# switch-backpack.net
KiCad netlist of a schematic drawn in EAGLE
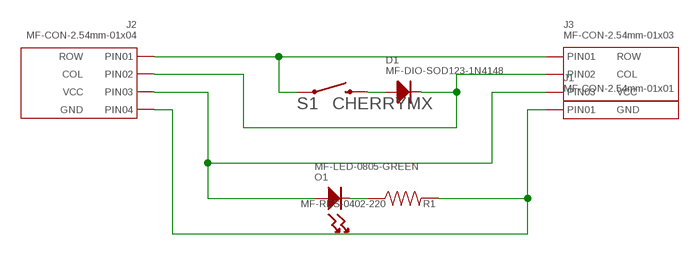
[diagram p0: schematic, sheet 1]

(export (version "E")
  (design (tool "Eeschema 10.0.6"))
  (components
    (comp (ref "D1")
      (value "MF-DIO-SOD123-1N4148")
      (footprint "eagle-import:SOD-123")
      (fields (field (name "HOUSEPART") "YES"))
      (libsource (lib "eagle-import") (part "DIODES_SOD-123_1N4148"))
    )
    (comp (ref "J1")
      (value "MF-CON-2.54mm-01x01")
      (footprint "eagle-import:PTH_2.54MM_01X01")
      (fields (field (name "HOUSEPART") "YES") (field (name "LABEL01") "GND"))
      (libsource (lib "eagle-import") (part "CON_01X01_PTH_2.54MM"))
    )
    (comp (ref "J2")
      (value "MF-CON-2.54mm-01x04")
      (footprint "eagle-import:PTH_2.54MM_01X04")
      (fields
        (field (name "HOUSEPART") "YES")
        (field (name "LABEL01") "ROW")
        (field (name "LABEL02") "COL")
        (field (name "LABEL03") "VCC")
        (field (name "LABEL04") "GND")
      )
      (libsource (lib "eagle-import") (part "CON_01X04_PTH_2.54MM"))
    )
    (comp (ref "J3")
      (value "MF-CON-2.54mm-01x03")
      (footprint "eagle-import:PTH_2.54MM_01X03")
      (fields
        (field (name "HOUSEPART") "YES")
        (field (name "LABEL01") "ROW")
        (field (name "LABEL02") "COL")
        (field (name "LABEL03") "VCC")
      )
      (libsource (lib "eagle-import") (part "CON_01X03_PTH_2.54MM"))
    )
    (comp (ref "O1")
      (value "MF-LED-0805-GREEN")
      (footprint "eagle-import:LED0805")
      (fields (field (name "HOUSEPART") "NO"))
      (libsource (lib "eagle-import") (part "LED_SINGLE-0805"))
    )
    (comp (ref "R1")
      (value "MF-RES-0402-220")
      (footprint "eagle-import:R0402")
      (libsource (lib "eagle-import") (part "RESISTOR_0402"))
    )
    (comp (ref "S1")
      (value "CHERRYMX")
      (footprint "eagle-import:CHERRYMX")
      (libsource (lib "eagle-import") (part "SWITCH-MOMENTARY-2CHERRYMX"))
    )
  )
  (nets
    (net (code "1") (name "Net-(J1-PIN1)") (class "Default")
      (node (ref "J1") (pin "P$1") (pinfunction "PIN1_P$1") (pintype "bidirectional"))
      (node (ref "J2") (pin "P$4") (pinfunction "PIN4_P$4") (pintype "bidirectional"))
      (node (ref "R1") (pin "P$2") (pinfunction "P$2_P$2") (pintype "passive"))
    )
    (net (code "2") (name "Net-(J2-PIN1)") (class "Default")
      (node (ref "J2") (pin "P$1") (pinfunction "PIN1_P$1") (pintype "bidirectional"))
      (node (ref "J3") (pin "P$1") (pinfunction "PIN1_P$1") (pintype "bidirectional"))
      (node (ref "S1") (pin "P$1") (pinfunction "1_P$1") (pintype "passive"))
    )
    (net (code "3") (name "Net-(J2-PIN2)") (class "Default")
      (node (ref "D1") (pin "CATHODE") (pinfunction "CATHODE_CATHODE") (pintype "bidirectional"))
      (node (ref "J2") (pin "P$2") (pinfunction "PIN2_P$2") (pintype "bidirectional"))
      (node (ref "J3") (pin "P$2") (pinfunction "PIN2_P$2") (pintype "bidirectional"))
    )
    (net (code "4") (name "Net-(J2-PIN3)") (class "Default")
      (node (ref "J2") (pin "P$3") (pinfunction "PIN3_P$3") (pintype "bidirectional"))
      (node (ref "J3") (pin "P$3") (pinfunction "PIN3_P$3") (pintype "bidirectional"))
      (node (ref "O1") (pin "ANODE") (pinfunction "ANODE_ANODE") (pintype "power_in"))
    )
    (net (code "5") (name "Net-(O1-PadCATHODE)") (class "Default")
      (node (ref "O1") (pin "CATHODE") (pinfunction "CATHODE_CATHODE") (pintype "power_in"))
      (node (ref "R1") (pin "P$1") (pinfunction "P$1_P$1") (pintype "passive"))
    )
    (net (code "6") (name "Net-(S1-2)") (class "Default")
      (node (ref "D1") (pin "ANODE") (pinfunction "ANODE_ANODE") (pintype "bidirectional"))
      (node (ref "S1") (pin "P$2") (pinfunction "2_P$2") (pintype "passive"))
    )
  )
)
